# psu.net
KiCad netlist of a schematic drawn in Altium Designer
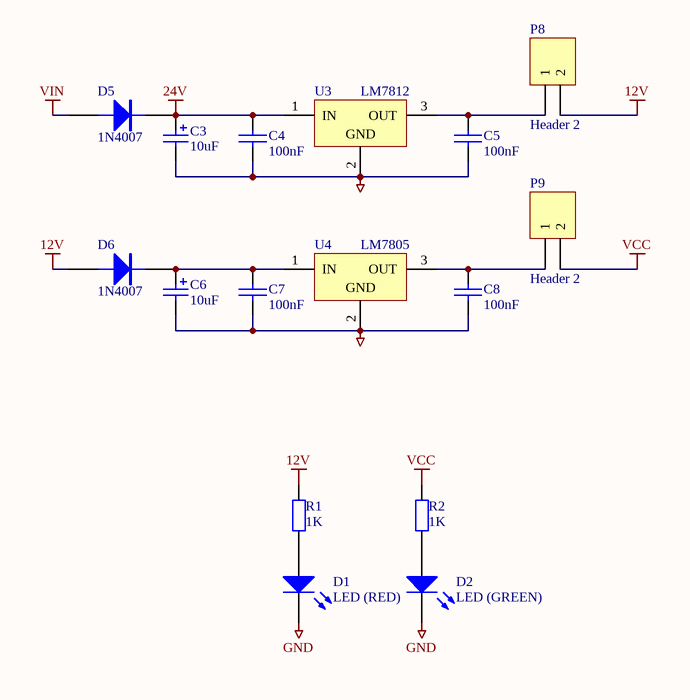
[diagram p0: psu.schdoc]

(export (version "E")
  (design (tool "Eeschema 10.0.6"))
  (components
    (comp (ref "C3")
      (value "10uF")
      (footprint "RB7.6-15")
      (description "CAPACITOR POLARISED TAG B CASE")
      (fields
        (field (name "MANUFACTURER") "Vishay/Sprague")
        (field (name "MOUSER PART NO.") "71-591D106X9020B2T15")
      )
      (libsource (lib "Mi-Call Schematic") (part "Cap Pol"))
    )
    (comp (ref "C4")
      (value "100nF")
      (footprint "CAP RADIAL 0.200")
      (description "CAPACITOR SMD 0603")
      (fields (field (name "MOUSER PART NO.") "81-GCM188R71C104KA7D") (field (name "MANUFACTURER") "Murata"))
      (libsource (lib "Mi-Call Schematic") (part "CAP"))
    )
    (comp (ref "C5")
      (value "100nF")
      (footprint "CAP RADIAL 0.200")
      (description "CAPACITOR SMD 0603")
      (fields (field (name "MOUSER PART NO.") "81-GCM188R71C104KA7D") (field (name "MANUFACTURER") "Murata"))
      (libsource (lib "Mi-Call Schematic") (part "CAP"))
    )
    (comp (ref "C6")
      (value "10uF")
      (footprint "RB7.6-15")
      (description "CAPACITOR POLARISED TAG B CASE")
      (fields
        (field (name "MANUFACTURER") "Vishay/Sprague")
        (field (name "MOUSER PART NO.") "71-591D106X9020B2T15")
      )
      (libsource (lib "Mi-Call Schematic") (part "Cap Pol"))
    )
    (comp (ref "C7")
      (value "100nF")
      (footprint "CAP RADIAL 0.200")
      (description "CAPACITOR SMD 0603")
      (fields (field (name "MOUSER PART NO.") "81-GCM188R71C104KA7D") (field (name "MANUFACTURER") "Murata"))
      (libsource (lib "Mi-Call Schematic") (part "CAP"))
    )
    (comp (ref "C8")
      (value "100nF")
      (footprint "CAP RADIAL 0.200")
      (description "CAPACITOR SMD 0603")
      (fields (field (name "MOUSER PART NO.") "81-GCM188R71C104KA7D") (field (name "MANUFACTURER") "Murata"))
      (libsource (lib "Mi-Call Schematic") (part "CAP"))
    )
    (comp (ref "D1")
      (value "LED (RED)")
      (footprint "LED(3D) 5MM VERTICAL (GREEN)")
      (description "3mm RED LED")
      (fields (field (name "MOUSER PART NO.") "604-WP132XIT") (field (name "FARNELL PART NO.") "1003393"))
      (libsource (lib "NASCO") (part "LED 3mm RED"))
    )
    (comp (ref "D2")
      (value "LED (GREEN)")
      (footprint "LED(3D) 5MM VERTICAL (GREEN)")
      (description "3mm RED LED")
      (fields (field (name "MOUSER PART NO.") "604-WP132XIT") (field (name "FARNELL PART NO.") "1003393"))
      (libsource (lib "NASCO") (part "LED 3mm RED"))
    )
    (comp (ref "D5")
      (value "1N4007")
      (footprint "DO-35")
      (description "DIODE, POWER")
      (fields (field (name "MOUSER PART NO.") "821-S1M") (field (name "MANUFACTURER") "TAIWAN SEMI"))
      (libsource (lib "*") (part "DIODE"))
    )
    (comp (ref "D6")
      (value "1N4007")
      (footprint "DO-35")
      (description "DIODE, POWER")
      (fields (field (name "MOUSER PART NO.") "821-S1M") (field (name "MANUFACTURER") "TAIWAN SEMI"))
      (libsource (lib "*") (part "DIODE"))
    )
    (comp (ref "P8")
      (value "Header 2")
      (footprint "HDR1X2")
      (description "Header, 2-Pin")
      (fields (field (name "PUBLISHER") "Altium Limited"))
      (libsource (lib "Miscellaneous Connectors") (part "Header 2"))
    )
    (comp (ref "P9")
      (value "Header 2")
      (footprint "HDR1X2")
      (description "Header, 2-Pin")
      (fields (field (name "PUBLISHER") "Altium Limited"))
      (libsource (lib "Miscellaneous Connectors") (part "Header 2"))
    )
    (comp (ref "R1")
      (value "1K")
      (footprint "AXIAL-0.4")
      (description "Resistor")
      (fields (field (name "Comment") "Res2") (field (name "PUBLISHER") "Altium Limited"))
      (libsource (lib "Miscellaneous Devices") (part "Res2"))
    )
    (comp (ref "R2")
      (value "1K")
      (footprint "AXIAL-0.4")
      (description "Resistor")
      (fields (field (name "Comment") "Res2") (field (name "PUBLISHER") "Altium Limited"))
      (libsource (lib "Miscellaneous Devices") (part "Res2"))
    )
    (comp (ref "U3")
      (value "LM7812")
      (footprint "TO-220")
      (description "3-Terminal Positive Fixed Voltage Regulator")
      (fields (field (name "MANUFACTURER") "Fairchild Semiconductor"))
      (libsource (lib "Motorola Power Mgt Voltage Regulator") (part "MC7805ACT"))
    )
    (comp (ref "U4")
      (value "LM7805")
      (footprint "TO-220")
      (description "3-Terminal Positive Fixed Voltage Regulator")
      (fields
        (field (name "MOUSER PART NO.") "512-LM7805CT")
        (field (name "MANUFACTURER") "Fairchild Semiconductor")
      )
      (libsource (lib "Motorola Power Mgt Voltage Regulator") (part "MC7805ACT"))
    )
  )
  (nets
    (net (code "1") (name "12V") (class "Default")
      (node (ref "D6") (pin "1") (pinfunction "A_1") (pintype "passive"))
      (node (ref "P8") (pin "2") (pinfunction "2_2") (pintype "passive"))
      (node (ref "R1") (pin "1") (pinfunction "1_1") (pintype "passive"))
    )
    (net (code "2") (name "24V") (class "Default")
      (node (ref "C3") (pin "1") (pinfunction "1_1") (pintype "passive"))
      (node (ref "C4") (pin "1") (pinfunction "1_1") (pintype "passive"))
      (node (ref "D5") (pin "2") (pinfunction "K_2") (pintype "passive"))
      (node (ref "U3") (pin "1") (pinfunction "IN_1") (pintype "power_in"))
    )
    (net (code "3") (name "GND") (class "Default")
      (node (ref "C3") (pin "2") (pinfunction "2_2") (pintype "passive"))
      (node (ref "C4") (pin "2") (pinfunction "2_2") (pintype "passive"))
      (node (ref "C5") (pin "2") (pinfunction "2_2") (pintype "passive"))
      (node (ref "C6") (pin "2") (pinfunction "2_2") (pintype "passive"))
      (node (ref "C7") (pin "2") (pinfunction "2_2") (pintype "passive"))
      (node (ref "C8") (pin "2") (pinfunction "2_2") (pintype "passive"))
      (node (ref "D1") (pin "2") (pinfunction "K_2") (pintype "passive"))
      (node (ref "D2") (pin "2") (pinfunction "K_2") (pintype "passive"))
      (node (ref "U3") (pin "2") (pinfunction "GND_2") (pintype "power_in"))
      (node (ref "U4") (pin "2") (pinfunction "GND_2") (pintype "power_in"))
    )
    (net (code "4") (name "Net-(D1-A)") (class "Default")
      (node (ref "D1") (pin "1") (pinfunction "A_1") (pintype "passive"))
      (node (ref "R1") (pin "2") (pinfunction "2_2") (pintype "passive"))
    )
    (net (code "5") (name "Net-(D2-A)") (class "Default")
      (node (ref "D2") (pin "1") (pinfunction "A_1") (pintype "passive"))
      (node (ref "R2") (pin "2") (pinfunction "2_2") (pintype "passive"))
    )
    (net (code "6") (name "Net-(D6-K)") (class "Default")
      (node (ref "C6") (pin "1") (pinfunction "1_1") (pintype "passive"))
      (node (ref "C7") (pin "1") (pinfunction "1_1") (pintype "passive"))
      (node (ref "D6") (pin "2") (pinfunction "K_2") (pintype "passive"))
      (node (ref "U4") (pin "1") (pinfunction "IN_1") (pintype "power_in"))
    )
    (net (code "7") (name "Net-(U3-OUT)") (class "Default")
      (node (ref "C5") (pin "1") (pinfunction "1_1") (pintype "passive"))
      (node (ref "P8") (pin "1") (pinfunction "1_1") (pintype "passive"))
      (node (ref "U3") (pin "3") (pinfunction "OUT_3") (pintype "power_in"))
    )
    (net (code "8") (name "Net-(U4-OUT)") (class "Default")
      (node (ref "C8") (pin "1") (pinfunction "1_1") (pintype "passive"))
      (node (ref "P9") (pin "1") (pinfunction "1_1") (pintype "passive"))
      (node (ref "U4") (pin "3") (pinfunction "OUT_3") (pintype "power_in"))
    )
    (net (code "9") (name "VCC") (class "Default")
      (node (ref "P9") (pin "2") (pinfunction "2_2") (pintype "passive"))
      (node (ref "R2") (pin "1") (pinfunction "1_1") (pintype "passive"))
    )
    (net (code "10") (name "VIN") (class "Default")
      (node (ref "D5") (pin "1") (pinfunction "A_1") (pintype "passive"))
    )
  )
)
